# BeVimExpansionBoard2.net
KiCad netlist of a schematic drawn in EAGLE
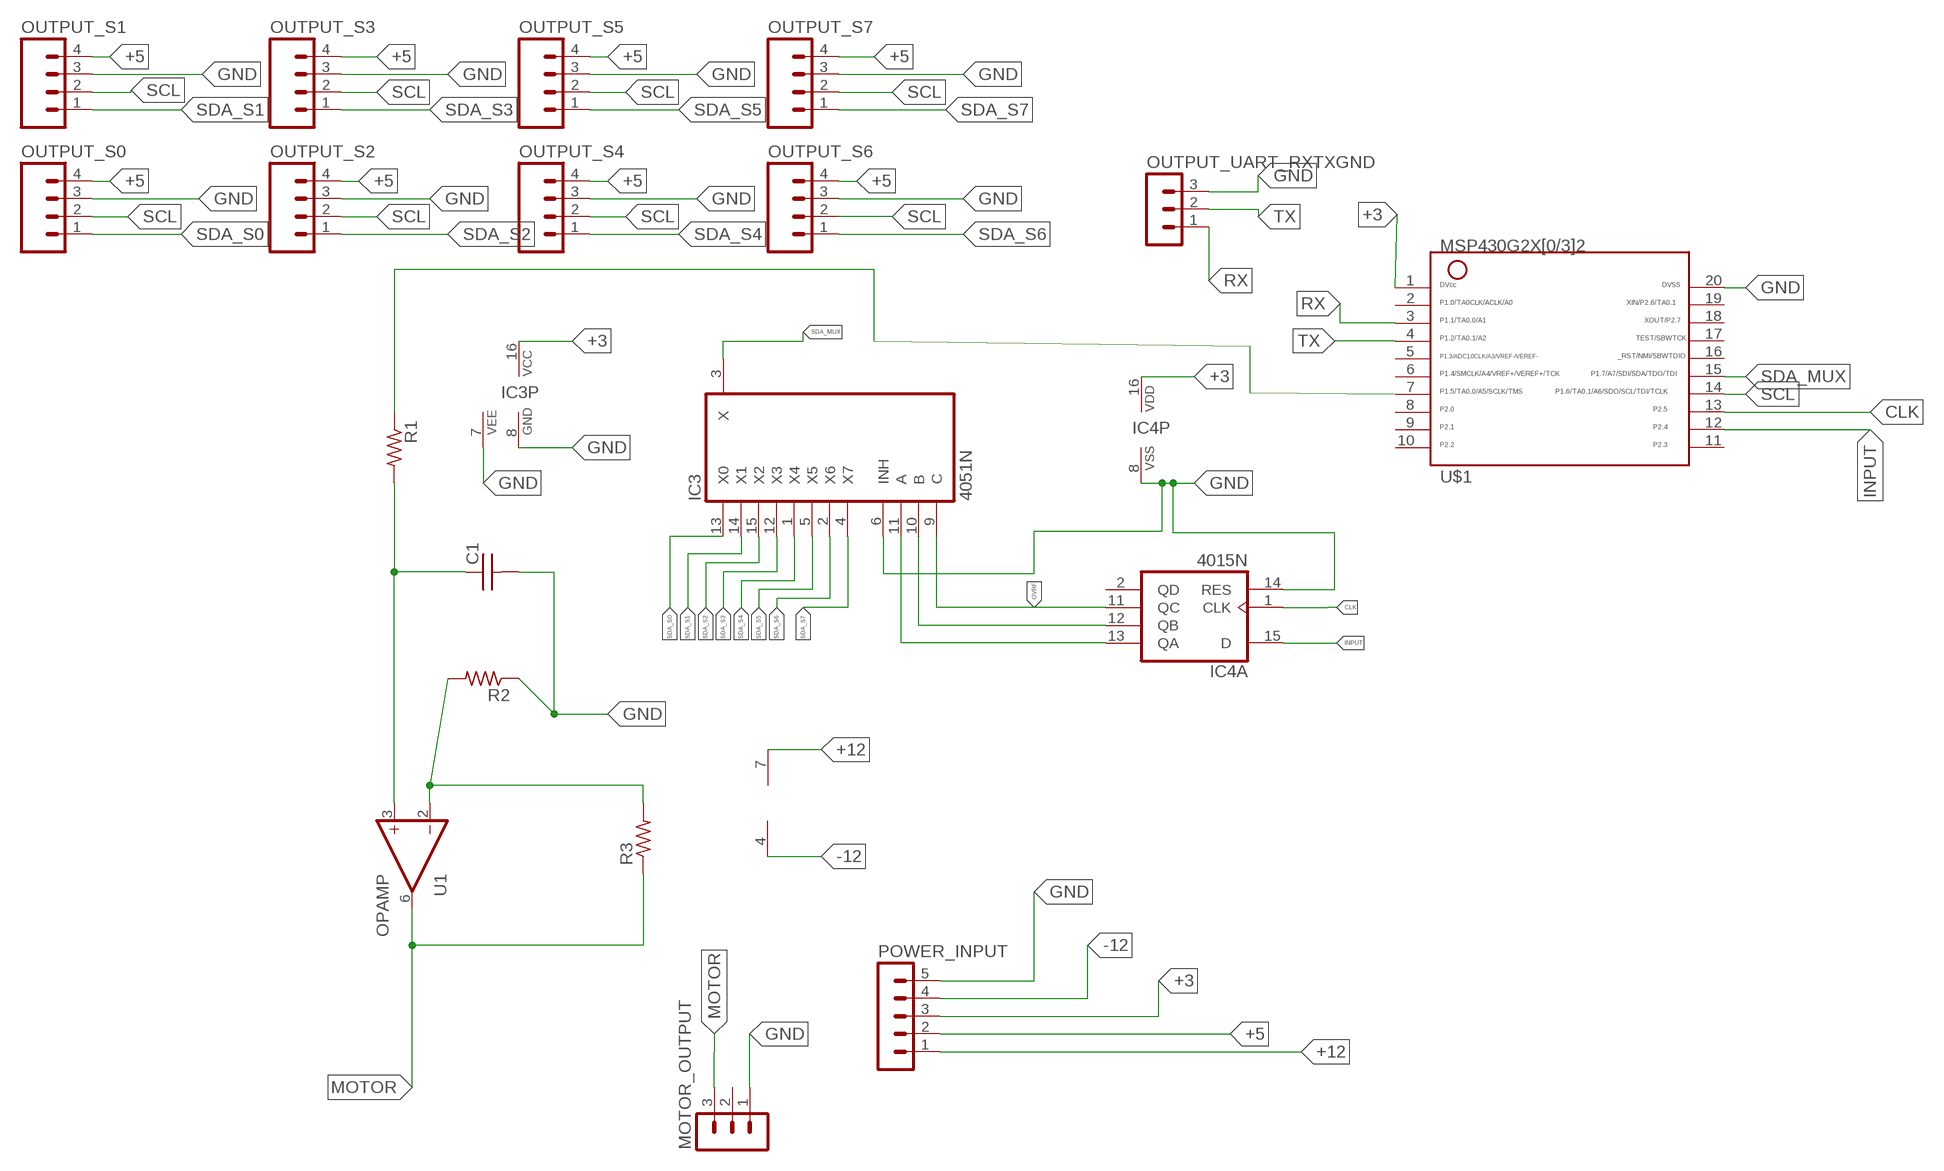
[diagram p0: schematic, sheet 1]

(export (version "E")
  (design (tool "Eeschema 10.0.6"))
  (components
    (comp (ref "C1")
      (value "CAPACITOR")
      (footprint "eagle-import:BOX-2.5MM-7.2MM")
      (libsource (lib "eagle-import") (part "CAPACITOR"))
    )
    (comp (ref "IC3")
      (value "4051N")
      (footprint "eagle-import:DIL16")
      (libsource (lib "eagle-import") (part "4051N"))
    )
    (comp (ref "IC4")
      (value "4015N")
      (footprint "eagle-import:DIL16")
      (libsource (lib "eagle-import") (part "4015N"))
    )
    (comp (ref "MOTOR_OUTPUT")
      (value "MA03-1")
      (footprint "eagle-import:MA03-1")
      (libsource (lib "eagle-import") (part "MA03-1"))
    )
    (comp (ref "OUTPUT_S0")
      (value "M04LOCK")
      (footprint "eagle-import:1X04_LOCK")
      (libsource (lib "eagle-import") (part "M04LOCK"))
    )
    (comp (ref "OUTPUT_S1")
      (value "M04LOCK")
      (footprint "eagle-import:1X04_LOCK")
      (libsource (lib "eagle-import") (part "M04LOCK"))
    )
    (comp (ref "OUTPUT_S2")
      (value "M04LOCK")
      (footprint "eagle-import:1X04_LOCK")
      (libsource (lib "eagle-import") (part "M04LOCK"))
    )
    (comp (ref "OUTPUT_S3")
      (value "M04LOCK")
      (footprint "eagle-import:1X04_LOCK")
      (libsource (lib "eagle-import") (part "M04LOCK"))
    )
    (comp (ref "OUTPUT_S4")
      (value "M04LOCK")
      (footprint "eagle-import:1X04_LOCK")
      (libsource (lib "eagle-import") (part "M04LOCK"))
    )
    (comp (ref "OUTPUT_S5")
      (value "M04LOCK")
      (footprint "eagle-import:1X04_LOCK")
      (libsource (lib "eagle-import") (part "M04LOCK"))
    )
    (comp (ref "OUTPUT_S6")
      (value "M04LOCK")
      (footprint "eagle-import:1X04_LOCK")
      (libsource (lib "eagle-import") (part "M04LOCK"))
    )
    (comp (ref "OUTPUT_S7")
      (value "M04LOCK")
      (footprint "eagle-import:1X04_LOCK")
      (libsource (lib "eagle-import") (part "M04LOCK"))
    )
    (comp (ref "OUTPUT_UART_RXTXGND")
      (value "MA03-1")
      (footprint "eagle-import:MA03-1")
      (libsource (lib "eagle-import") (part "MA03-1"))
    )
    (comp (ref "POWER_INPUT")
      (value "MA05-1")
      (footprint "eagle-import:MA05-1")
      (libsource (lib "eagle-import") (part "MA05-1"))
    )
    (comp (ref "R1")
      (value "RESISTOR")
      (footprint "eagle-import:0.25W-0.3IN")
      (libsource (lib "eagle-import") (part "RESISTOR"))
    )
    (comp (ref "R2")
      (value "RESISTOR")
      (footprint "eagle-import:0.25W-0.3IN")
      (libsource (lib "eagle-import") (part "RESISTOR"))
    )
    (comp (ref "R3")
      (value "RESISTOR")
      (footprint "eagle-import:0.25W-0.3IN")
      (libsource (lib "eagle-import") (part "RESISTOR"))
    )
    (comp (ref "U$1")
      (value "G2X[0/3]2---N20")
      (footprint "eagle-import:N20")
      (libsource (lib "eagle-import") (part "G2X[0/3]2---N20"))
    )
    (comp (ref "U1")
      (value "OPAMP")
      (footprint "eagle-import:DIP8")
      (libsource (lib "eagle-import") (part "OPAMP"))
    )
  )
  (nets
    (net (code "1") (name "+3") (class "Default")
      (node (ref "IC3") (pin "16") (pinfunction "VCC_16") (pintype "power_in"))
      (node (ref "IC4") (pin "16") (pinfunction "VDD_16") (pintype "power_in"))
      (node (ref "POWER_INPUT") (pin "3") (pinfunction "3_3") (pintype "passive"))
      (node (ref "U$1") (pin "1") (pinfunction "1_1") (pintype "bidirectional"))
    )
    (net (code "2") (name "+5") (class "Default")
      (node (ref "OUTPUT_S0") (pin "4") (pinfunction "4_4") (pintype "passive"))
      (node (ref "OUTPUT_S1") (pin "4") (pinfunction "4_4") (pintype "passive"))
      (node (ref "OUTPUT_S2") (pin "4") (pinfunction "4_4") (pintype "passive"))
      (node (ref "OUTPUT_S3") (pin "4") (pinfunction "4_4") (pintype "passive"))
      (node (ref "OUTPUT_S4") (pin "4") (pinfunction "4_4") (pintype "passive"))
      (node (ref "OUTPUT_S5") (pin "4") (pinfunction "4_4") (pintype "passive"))
      (node (ref "OUTPUT_S6") (pin "4") (pinfunction "4_4") (pintype "passive"))
      (node (ref "OUTPUT_S7") (pin "4") (pinfunction "4_4") (pintype "passive"))
      (node (ref "POWER_INPUT") (pin "2") (pinfunction "2_2") (pintype "passive"))
    )
    (net (code "3") (name "+12") (class "Default")
      (node (ref "POWER_INPUT") (pin "1") (pinfunction "1_1") (pintype "passive"))
      (node (ref "U1") (pin "7") (pinfunction "VCC_7") (pintype "power_in"))
    )
    (net (code "4") (name "-12") (class "Default")
      (node (ref "POWER_INPUT") (pin "4") (pinfunction "4_4") (pintype "passive"))
      (node (ref "U1") (pin "4") (pinfunction "VEE_4") (pintype "power_in"))
    )
    (net (code "5") (name "CLK") (class "Default")
      (node (ref "IC4") (pin "1") (pinfunction "CLK_1") (pintype "input"))
      (node (ref "U$1") (pin "13") (pinfunction "13_13") (pintype "bidirectional"))
    )
    (net (code "6") (name "GND") (class "Default")
      (node (ref "C1") (pin "P$2") (pinfunction "2_P$2") (pintype "passive"))
      (node (ref "IC3") (pin "6") (pinfunction "INH_6") (pintype "input"))
      (node (ref "IC3") (pin "7") (pinfunction "VEE_7") (pintype "power_in"))
      (node (ref "IC3") (pin "8") (pinfunction "GND_8") (pintype "power_in"))
      (node (ref "IC4") (pin "14") (pinfunction "RES_14") (pintype "input"))
      (node (ref "IC4") (pin "8") (pinfunction "VSS_8") (pintype "power_in"))
      (node (ref "MOTOR_OUTPUT") (pin "1") (pinfunction "1_1") (pintype "passive"))
      (node (ref "OUTPUT_S0") (pin "3") (pinfunction "3_3") (pintype "passive"))
      (node (ref "OUTPUT_S1") (pin "3") (pinfunction "3_3") (pintype "passive"))
      (node (ref "OUTPUT_S2") (pin "3") (pinfunction "3_3") (pintype "passive"))
      (node (ref "OUTPUT_S3") (pin "3") (pinfunction "3_3") (pintype "passive"))
      (node (ref "OUTPUT_S4") (pin "3") (pinfunction "3_3") (pintype "passive"))
      (node (ref "OUTPUT_S5") (pin "3") (pinfunction "3_3") (pintype "passive"))
      (node (ref "OUTPUT_S6") (pin "3") (pinfunction "3_3") (pintype "passive"))
      (node (ref "OUTPUT_S7") (pin "3") (pinfunction "3_3") (pintype "passive"))
      (node (ref "OUTPUT_UART_RXTXGND") (pin "3") (pinfunction "3_3") (pintype "passive"))
      (node (ref "POWER_INPUT") (pin "5") (pinfunction "5_5") (pintype "passive"))
      (node (ref "R2") (pin "1") (pinfunction "1_1") (pintype "passive"))
      (node (ref "U$1") (pin "20") (pinfunction "20_20") (pintype "bidirectional"))
    )
    (net (code "7") (name "INPUT") (class "Default")
      (node (ref "IC4") (pin "15") (pinfunction "D_15") (pintype "input"))
      (node (ref "U$1") (pin "12") (pinfunction "12_12") (pintype "bidirectional"))
    )
    (net (code "8") (name "MOTOR") (class "Default")
      (node (ref "MOTOR_OUTPUT") (pin "3") (pinfunction "3_3") (pintype "passive"))
      (node (ref "R3") (pin "1") (pinfunction "1_1") (pintype "passive"))
      (node (ref "U1") (pin "6") (pinfunction "OUT_6") (pintype "output"))
    )
    (net (code "9") (name "Net-(C1-1)") (class "Default")
      (node (ref "C1") (pin "P$1") (pinfunction "1_P$1") (pintype "passive"))
      (node (ref "R1") (pin "2") (pinfunction "2_2") (pintype "passive"))
      (node (ref "U1") (pin "3") (pinfunction "IN+_3") (pintype "input"))
    )
    (net (code "10") (name "Net-(IC3A-A)") (class "Default")
      (node (ref "IC3") (pin "11") (pinfunction "A_11") (pintype "input"))
      (node (ref "IC4") (pin "13") (pinfunction "QA_13") (pintype "output"))
    )
    (net (code "11") (name "Net-(IC3A-B)") (class "Default")
      (node (ref "IC3") (pin "10") (pinfunction "B_10") (pintype "input"))
      (node (ref "IC4") (pin "12") (pinfunction "QB_12") (pintype "output"))
    )
    (net (code "12") (name "Net-(R1-Pad1)") (class "Default")
      (node (ref "R1") (pin "1") (pinfunction "1_1") (pintype "passive"))
      (node (ref "U$1") (pin "7") (pinfunction "7_7") (pintype "bidirectional"))
    )
    (net (code "13") (name "Net-(U1A-IN-)") (class "Default")
      (node (ref "R2") (pin "2") (pinfunction "2_2") (pintype "passive"))
      (node (ref "R3") (pin "2") (pinfunction "2_2") (pintype "passive"))
      (node (ref "U1") (pin "2") (pinfunction "IN-_2") (pintype "input"))
    )
    (net (code "14") (name "OVRF") (class "Default")
      (node (ref "IC3") (pin "9") (pinfunction "C_9") (pintype "input"))
      (node (ref "IC4") (pin "11") (pinfunction "QC_11") (pintype "output"))
    )
    (net (code "15") (name "RX") (class "Default")
      (node (ref "OUTPUT_UART_RXTXGND") (pin "1") (pinfunction "1_1") (pintype "passive"))
      (node (ref "U$1") (pin "3") (pinfunction "3_3") (pintype "bidirectional"))
    )
    (net (code "16") (name "SCL") (class "Default")
      (node (ref "OUTPUT_S0") (pin "2") (pinfunction "2_2") (pintype "passive"))
      (node (ref "OUTPUT_S1") (pin "2") (pinfunction "2_2") (pintype "passive"))
      (node (ref "OUTPUT_S2") (pin "2") (pinfunction "2_2") (pintype "passive"))
      (node (ref "OUTPUT_S3") (pin "2") (pinfunction "2_2") (pintype "passive"))
      (node (ref "OUTPUT_S4") (pin "2") (pinfunction "2_2") (pintype "passive"))
      (node (ref "OUTPUT_S5") (pin "2") (pinfunction "2_2") (pintype "passive"))
      (node (ref "OUTPUT_S6") (pin "2") (pinfunction "2_2") (pintype "passive"))
      (node (ref "OUTPUT_S7") (pin "2") (pinfunction "2_2") (pintype "passive"))
      (node (ref "U$1") (pin "14") (pinfunction "14_14") (pintype "bidirectional"))
    )
    (net (code "17") (name "SDA_MUX") (class "Default")
      (node (ref "IC3") (pin "3") (pinfunction "X_3") (pintype "bidirectional"))
      (node (ref "U$1") (pin "15") (pinfunction "15_15") (pintype "bidirectional"))
    )
    (net (code "18") (name "SDA_S0") (class "Default")
      (node (ref "IC3") (pin "13") (pinfunction "X0_13") (pintype "bidirectional"))
      (node (ref "OUTPUT_S0") (pin "1") (pinfunction "1_1") (pintype "passive"))
    )
    (net (code "19") (name "SDA_S1") (class "Default")
      (node (ref "IC3") (pin "14") (pinfunction "X1_14") (pintype "bidirectional"))
      (node (ref "OUTPUT_S1") (pin "1") (pinfunction "1_1") (pintype "passive"))
    )
    (net (code "20") (name "SDA_S2") (class "Default")
      (node (ref "IC3") (pin "15") (pinfunction "X2_15") (pintype "bidirectional"))
      (node (ref "OUTPUT_S2") (pin "1") (pinfunction "1_1") (pintype "passive"))
    )
    (net (code "21") (name "SDA_S3") (class "Default")
      (node (ref "IC3") (pin "12") (pinfunction "X3_12") (pintype "bidirectional"))
      (node (ref "OUTPUT_S3") (pin "1") (pinfunction "1_1") (pintype "passive"))
    )
    (net (code "22") (name "SDA_S4") (class "Default")
      (node (ref "IC3") (pin "1") (pinfunction "X4_1") (pintype "bidirectional"))
      (node (ref "OUTPUT_S4") (pin "1") (pinfunction "1_1") (pintype "passive"))
    )
    (net (code "23") (name "SDA_S5") (class "Default")
      (node (ref "IC3") (pin "5") (pinfunction "X5_5") (pintype "bidirectional"))
      (node (ref "OUTPUT_S5") (pin "1") (pinfunction "1_1") (pintype "passive"))
    )
    (net (code "24") (name "SDA_S6") (class "Default")
      (node (ref "IC3") (pin "2") (pinfunction "X6_2") (pintype "bidirectional"))
      (node (ref "OUTPUT_S6") (pin "1") (pinfunction "1_1") (pintype "passive"))
    )
    (net (code "25") (name "SDA_S7") (class "Default")
      (node (ref "IC3") (pin "4") (pinfunction "X7_4") (pintype "bidirectional"))
      (node (ref "OUTPUT_S7") (pin "1") (pinfunction "1_1") (pintype "passive"))
    )
    (net (code "26") (name "TX") (class "Default")
      (node (ref "OUTPUT_UART_RXTXGND") (pin "2") (pinfunction "2_2") (pintype "passive"))
      (node (ref "U$1") (pin "4") (pinfunction "4_4") (pintype "bidirectional"))
    )
    (net (code "27") (name "unconnected-(IC4A-QD-Pad2)") (class "Default")
      (node (ref "IC4") (pin "2") (pinfunction "QD_2") (pintype "output"))
    )
    (net (code "28") (name "unconnected-(MOTOR_OUTPUT-Pad2)") (class "Default")
      (node (ref "MOTOR_OUTPUT") (pin "2") (pinfunction "2_2") (pintype "passive"))
    )
    (net (code "29") (name "unconnected-(U$1-Pad2)") (class "Default")
      (node (ref "U$1") (pin "2") (pinfunction "2_2") (pintype "bidirectional"))
    )
    (net (code "30") (name "unconnected-(U$1-Pad5)") (class "Default")
      (node (ref "U$1") (pin "5") (pinfunction "5_5") (pintype "bidirectional"))
    )
    (net (code "31") (name "unconnected-(U$1-Pad6)") (class "Default")
      (node (ref "U$1") (pin "6") (pinfunction "6_6") (pintype "bidirectional"))
    )
    (net (code "32") (name "unconnected-(U$1-Pad8)") (class "Default")
      (node (ref "U$1") (pin "8") (pinfunction "8_8") (pintype "bidirectional"))
    )
    (net (code "33") (name "unconnected-(U$1-Pad9)") (class "Default")
      (node (ref "U$1") (pin "9") (pinfunction "9_9") (pintype "bidirectional"))
    )
    (net (code "34") (name "unconnected-(U$1-Pad10)") (class "Default")
      (node (ref "U$1") (pin "10") (pinfunction "10_10") (pintype "bidirectional"))
    )
    (net (code "35") (name "unconnected-(U$1-Pad11)") (class "Default")
      (node (ref "U$1") (pin "11") (pinfunction "11_11") (pintype "bidirectional"))
    )
    (net (code "36") (name "unconnected-(U$1-Pad16)") (class "Default")
      (node (ref "U$1") (pin "16") (pinfunction "16_16") (pintype "bidirectional"))
    )
    (net (code "37") (name "unconnected-(U$1-Pad17)") (class "Default")
      (node (ref "U$1") (pin "17") (pinfunction "17_17") (pintype "bidirectional"))
    )
    (net (code "38") (name "unconnected-(U$1-Pad18)") (class "Default")
      (node (ref "U$1") (pin "18") (pinfunction "18_18") (pintype "bidirectional"))
    )
    (net (code "39") (name "unconnected-(U$1-Pad19)") (class "Default")
      (node (ref "U$1") (pin "19") (pinfunction "19_19") (pintype "bidirectional"))
    )
  )
)
